# PCB-base.net
KiCad netlist of a schematic drawn in EAGLE
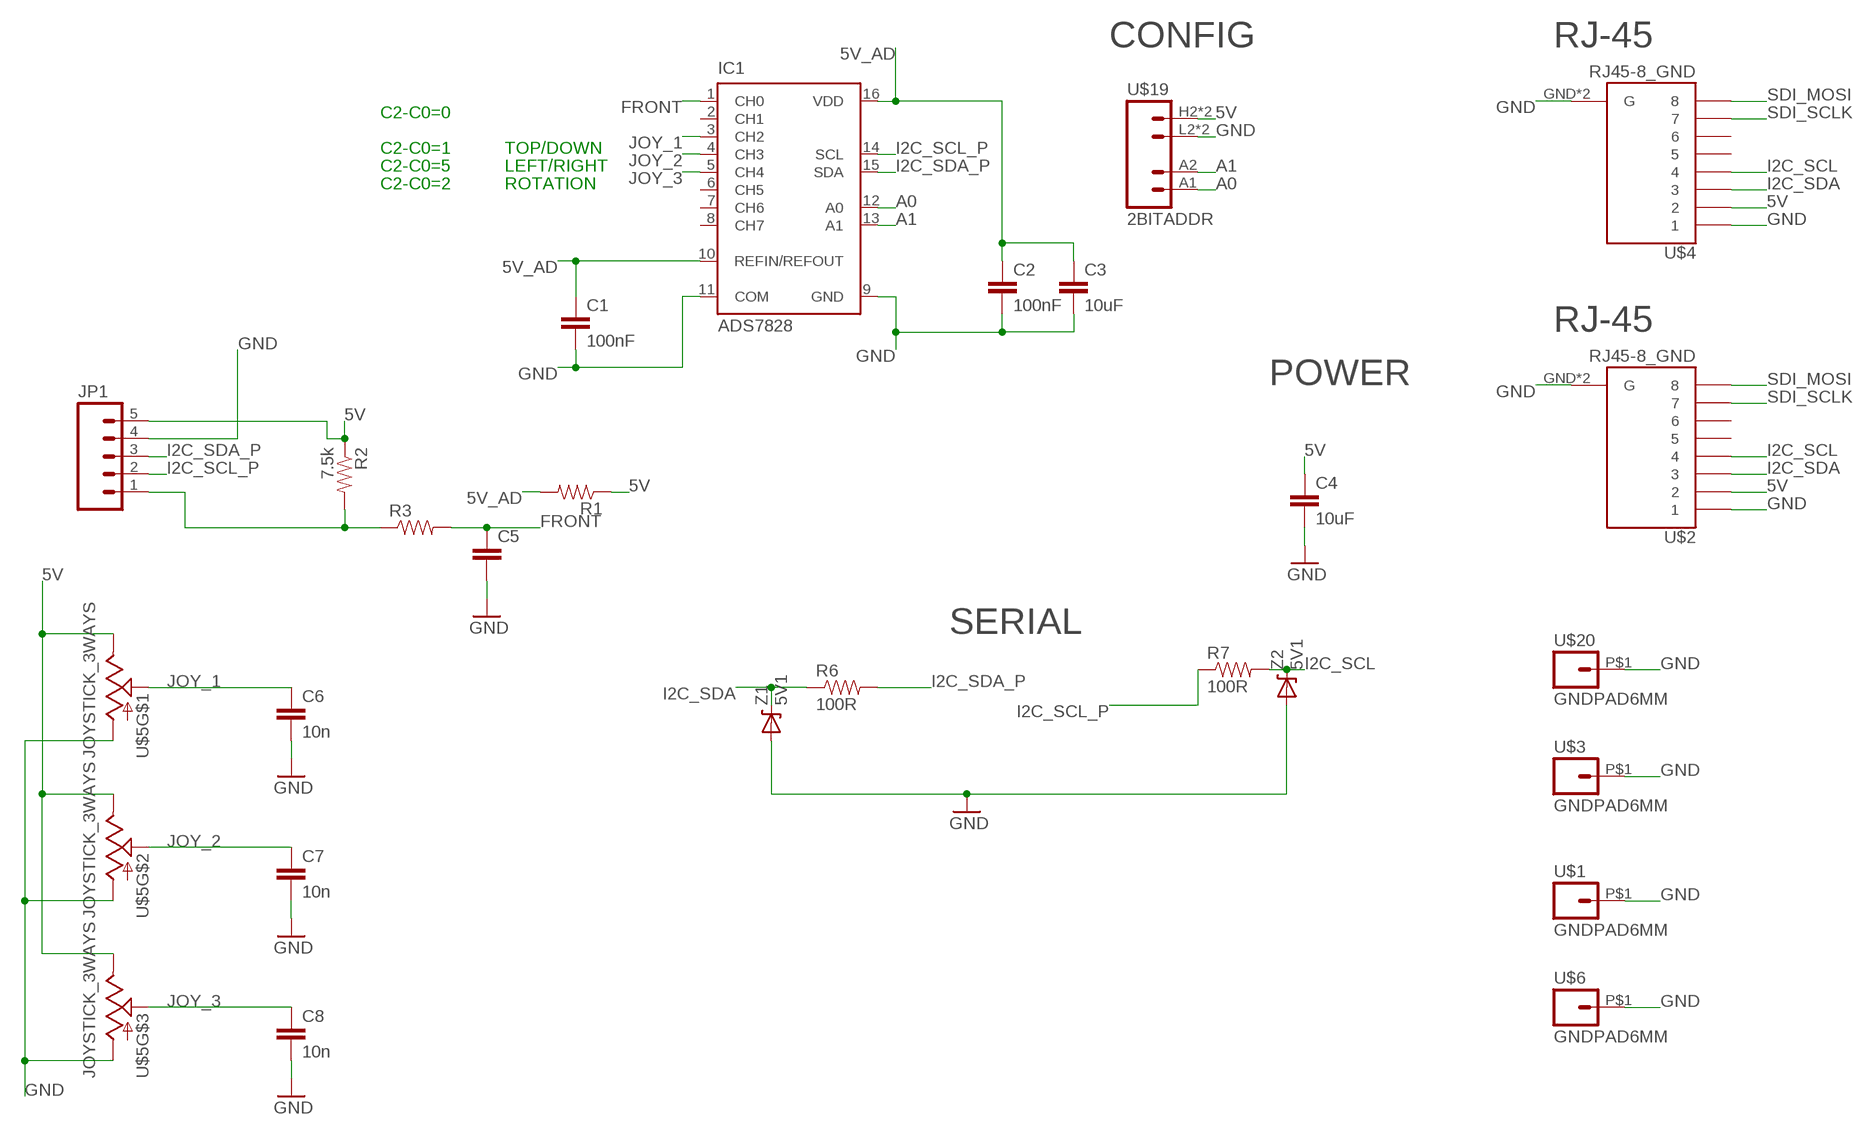
[diagram p0: schematic, sheet 1]

(export (version "E")
  (design (tool "Eeschema 10.0.6"))
  (components
    (comp (ref "C1")
      (value "100nF")
      (footprint "eagle-import:0603-CAP")
      (libsource (lib "eagle-import") (part "CAP0603-CAP"))
    )
    (comp (ref "C2")
      (value "100nF")
      (footprint "eagle-import:0603-CAP")
      (libsource (lib "eagle-import") (part "CAP0603-CAP"))
    )
    (comp (ref "C3")
      (value "10uF")
      (footprint "eagle-import:0805")
      (libsource (lib "eagle-import") (part "CAP0805"))
    )
    (comp (ref "C4")
      (value "10uF")
      (footprint "eagle-import:0805")
      (libsource (lib "eagle-import") (part "CAP0805"))
    )
    (comp (ref "C5")
      (value "CAP0603-CAP")
      (footprint "eagle-import:0603-CAP")
      (libsource (lib "eagle-import") (part "CAP0603-CAP"))
    )
    (comp (ref "C6")
      (value "10n")
      (footprint "eagle-import:0603-CAP")
      (libsource (lib "eagle-import") (part "CAP0603-CAP"))
    )
    (comp (ref "C7")
      (value "10n")
      (footprint "eagle-import:0603-CAP")
      (libsource (lib "eagle-import") (part "CAP0603-CAP"))
    )
    (comp (ref "C8")
      (value "10n")
      (footprint "eagle-import:0603-CAP")
      (libsource (lib "eagle-import") (part "CAP0603-CAP"))
    )
    (comp (ref "IC1")
      (value "ADS7828")
      (footprint "eagle-import:TSSOP16-PW")
      (fields (field (name "MF") "TEXAS INSTRUMENTS") (field (name "MPN") "ADS7828E/250"))
      (libsource (lib "eagle-import") (part "ADS7828"))
    )
    (comp (ref "JP1")
      (value "M05PTH")
      (footprint "eagle-import:1X05")
      (libsource (lib "eagle-import") (part "M05PTH"))
    )
    (comp (ref "R1")
      (value "RESISTOR0603-RES")
      (footprint "eagle-import:0603-RES")
      (libsource (lib "eagle-import") (part "RESISTOR0603-RES"))
    )
    (comp (ref "R2")
      (value "7.5k")
      (footprint "eagle-import:0603-RES")
      (libsource (lib "eagle-import") (part "RESISTOR0603-RES"))
    )
    (comp (ref "R3")
      (value "RESISTOR0603-RES")
      (footprint "eagle-import:0603-RES")
      (libsource (lib "eagle-import") (part "RESISTOR0603-RES"))
    )
    (comp (ref "R6")
      (value "100R")
      (footprint "eagle-import:0603-RES")
      (libsource (lib "eagle-import") (part "RESISTOR0603-RES"))
    )
    (comp (ref "R7")
      (value "100R")
      (footprint "eagle-import:0603-RES")
      (libsource (lib "eagle-import") (part "RESISTOR0603-RES"))
    )
    (comp (ref "U$1")
      (value "GNDPAD6MM")
      (footprint "eagle-import:3.2MMPAD6MM")
      (libsource (lib "eagle-import") (part "GNDPAD6MM"))
    )
    (comp (ref "U$2")
      (value "RJ45-8_GND")
      (footprint "eagle-import:RJ45-8_GND")
      (libsource (lib "eagle-import") (part "RJ45-8_GND"))
    )
    (comp (ref "U$3")
      (value "GNDPAD6MM")
      (footprint "eagle-import:3.2MMPAD6MM")
      (libsource (lib "eagle-import") (part "GNDPAD6MM"))
    )
    (comp (ref "U$4")
      (value "RJ45-8_GND")
      (footprint "eagle-import:RJ45-8_GND")
      (libsource (lib "eagle-import") (part "RJ45-8_GND"))
    )
    (comp (ref "U$5")
      (value "JOYSTICK_3WAYS")
      (footprint "eagle-import:JOYSTICK")
      (libsource (lib "eagle-import") (part "JOYSTICK_3WAYS"))
    )
    (comp (ref "U$6")
      (value "GNDPAD6MM")
      (footprint "eagle-import:3.2MMPAD6MM")
      (libsource (lib "eagle-import") (part "GNDPAD6MM"))
    )
    (comp (ref "U$19")
      (value "2BITADDR")
      (footprint "eagle-import:2BITADDR")
      (libsource (lib "eagle-import") (part "2BITADDR"))
    )
    (comp (ref "U$20")
      (value "GNDPAD6MM")
      (footprint "eagle-import:3.2MMPAD6MM")
      (libsource (lib "eagle-import") (part "GNDPAD6MM"))
    )
    (comp (ref "Z1")
      (value "5V1")
      (footprint "eagle-import:SMB-DIODE")
      (libsource (lib "eagle-import") (part "DIODE-ZENERSMB"))
    )
    (comp (ref "Z2")
      (value "5V1")
      (footprint "eagle-import:SMB-DIODE")
      (libsource (lib "eagle-import") (part "DIODE-ZENERSMB"))
    )
  )
  (nets
    (net (code "1") (name "/5V") (class "Default")
      (node (ref "C4") (pin "1") (pinfunction "1_1") (pintype "passive"))
      (node (ref "JP1") (pin "5") (pinfunction "5_5") (pintype "passive"))
      (node (ref "R1") (pin "1") (pinfunction "1_1") (pintype "passive"))
      (node (ref "R2") (pin "1") (pinfunction "1_1") (pintype "passive"))
      (node (ref "U$19") (pin "H2") (pinfunction "VCC_H2") (pintype "passive"))
      (node (ref "U$19") (pin "H3") (pinfunction "VCC_H3") (pintype "passive"))
      (node (ref "U$2") (pin "2") (pinfunction "2_2") (pintype "bidirectional"))
      (node (ref "U$4") (pin "2") (pinfunction "2_2") (pintype "bidirectional"))
      (node (ref "U$5") (pin "LR_V") (pinfunction "E_LR_V") (pintype "passive"))
      (node (ref "U$5") (pin "ROT_V") (pinfunction "E_ROT_V") (pintype "passive"))
      (node (ref "U$5") (pin "UD_V") (pinfunction "E_UD_V") (pintype "passive"))
    )
    (net (code "2") (name "/5V_AD") (class "Default")
      (node (ref "C1") (pin "1") (pinfunction "1_1") (pintype "passive"))
      (node (ref "C2") (pin "1") (pinfunction "1_1") (pintype "passive"))
      (node (ref "C3") (pin "1") (pinfunction "1_1") (pintype "passive"))
      (node (ref "IC1") (pin "10") (pinfunction "REFIN/REFOUT_10") (pintype "passive"))
      (node (ref "IC1") (pin "16") (pinfunction "VDD_16") (pintype "power_in"))
      (node (ref "R1") (pin "2") (pinfunction "2_2") (pintype "passive"))
    )
    (net (code "3") (name "/A0") (class "Default")
      (node (ref "IC1") (pin "12") (pinfunction "A0_12") (pintype "input"))
      (node (ref "U$19") (pin "A1") (pinfunction "A1_A1") (pintype "passive"))
    )
    (net (code "4") (name "/A1") (class "Default")
      (node (ref "IC1") (pin "13") (pinfunction "A1_13") (pintype "input"))
      (node (ref "U$19") (pin "A2") (pinfunction "A2_A2") (pintype "passive"))
    )
    (net (code "5") (name "/FRONT") (class "Default")
      (node (ref "C5") (pin "1") (pinfunction "1_1") (pintype "passive"))
      (node (ref "IC1") (pin "1") (pinfunction "CH0_1") (pintype "input"))
      (node (ref "R3") (pin "2") (pinfunction "2_2") (pintype "passive"))
    )
    (net (code "6") (name "/I2C_SCL") (class "Default")
      (node (ref "R7") (pin "2") (pinfunction "2_2") (pintype "passive"))
      (node (ref "U$2") (pin "4") (pinfunction "4_4") (pintype "bidirectional"))
      (node (ref "U$4") (pin "4") (pinfunction "4_4") (pintype "bidirectional"))
      (node (ref "Z2") (pin "C") (pinfunction "C_C") (pintype "passive"))
    )
    (net (code "7") (name "/I2C_SCL_P") (class "Default")
      (node (ref "IC1") (pin "14") (pinfunction "SCL_14") (pintype "input"))
      (node (ref "JP1") (pin "2") (pinfunction "2_2") (pintype "passive"))
      (node (ref "R7") (pin "1") (pinfunction "1_1") (pintype "passive"))
    )
    (net (code "8") (name "/I2C_SDA") (class "Default")
      (node (ref "R6") (pin "1") (pinfunction "1_1") (pintype "passive"))
      (node (ref "U$2") (pin "3") (pinfunction "3_3") (pintype "bidirectional"))
      (node (ref "U$4") (pin "3") (pinfunction "3_3") (pintype "bidirectional"))
      (node (ref "Z1") (pin "C") (pinfunction "C_C") (pintype "passive"))
    )
    (net (code "9") (name "/I2C_SDA_P") (class "Default")
      (node (ref "IC1") (pin "15") (pinfunction "SDA_15") (pintype "bidirectional"))
      (node (ref "JP1") (pin "3") (pinfunction "3_3") (pintype "passive"))
      (node (ref "R6") (pin "2") (pinfunction "2_2") (pintype "passive"))
    )
    (net (code "10") (name "/JOY_1") (class "Default")
      (node (ref "C6") (pin "1") (pinfunction "1_1") (pintype "passive"))
      (node (ref "IC1") (pin "3") (pinfunction "CH2_3") (pintype "input"))
      (node (ref "U$5") (pin "LR_C") (pinfunction "S_LR_C") (pintype "passive"))
    )
    (net (code "11") (name "/JOY_2") (class "Default")
      (node (ref "C7") (pin "1") (pinfunction "1_1") (pintype "passive"))
      (node (ref "IC1") (pin "4") (pinfunction "CH3_4") (pintype "input"))
      (node (ref "U$5") (pin "UD_C") (pinfunction "S_UD_C") (pintype "passive"))
    )
    (net (code "12") (name "/JOY_3") (class "Default")
      (node (ref "C8") (pin "1") (pinfunction "1_1") (pintype "passive"))
      (node (ref "IC1") (pin "5") (pinfunction "CH4_5") (pintype "input"))
      (node (ref "U$5") (pin "ROT_C") (pinfunction "S_ROT_C") (pintype "passive"))
    )
    (net (code "13") (name "/SDI_MOSI") (class "Default")
      (node (ref "U$2") (pin "8") (pinfunction "8_8") (pintype "bidirectional"))
      (node (ref "U$4") (pin "8") (pinfunction "8_8") (pintype "bidirectional"))
    )
    (net (code "14") (name "/SDI_SCLK") (class "Default")
      (node (ref "U$2") (pin "7") (pinfunction "7_7") (pintype "bidirectional"))
      (node (ref "U$4") (pin "7") (pinfunction "7_7") (pintype "bidirectional"))
    )
    (net (code "15") (name "GND") (class "Default")
      (node (ref "C1") (pin "2") (pinfunction "2_2") (pintype "passive"))
      (node (ref "C2") (pin "2") (pinfunction "2_2") (pintype "passive"))
      (node (ref "C3") (pin "2") (pinfunction "2_2") (pintype "passive"))
      (node (ref "C4") (pin "2") (pinfunction "2_2") (pintype "passive"))
      (node (ref "C5") (pin "2") (pinfunction "2_2") (pintype "passive"))
      (node (ref "C6") (pin "2") (pinfunction "2_2") (pintype "passive"))
      (node (ref "C7") (pin "2") (pinfunction "2_2") (pintype "passive"))
      (node (ref "C8") (pin "2") (pinfunction "2_2") (pintype "passive"))
      (node (ref "IC1") (pin "11") (pinfunction "COM_11") (pintype "input"))
      (node (ref "IC1") (pin "9") (pinfunction "GND_9") (pintype "power_in"))
      (node (ref "JP1") (pin "4") (pinfunction "4_4") (pintype "passive"))
      (node (ref "U$1") (pin "P$1") (pinfunction "1_P$1") (pintype "passive"))
      (node (ref "U$19") (pin "L2") (pinfunction "GND_L2") (pintype "passive"))
      (node (ref "U$19") (pin "L3") (pinfunction "GND_L3") (pintype "passive"))
      (node (ref "U$2") (pin "1") (pinfunction "1_1") (pintype "bidirectional"))
      (node (ref "U$2") (pin "GND") (pinfunction "G_GND") (pintype "power_in"))
      (node (ref "U$2") (pin "GND1") (pinfunction "G_GND1") (pintype "power_in"))
      (node (ref "U$20") (pin "P$1") (pinfunction "1_P$1") (pintype "passive"))
      (node (ref "U$3") (pin "P$1") (pinfunction "1_P$1") (pintype "passive"))
      (node (ref "U$4") (pin "1") (pinfunction "1_1") (pintype "bidirectional"))
      (node (ref "U$4") (pin "GND") (pinfunction "G_GND") (pintype "power_in"))
      (node (ref "U$4") (pin "GND1") (pinfunction "G_GND1") (pintype "power_in"))
      (node (ref "U$5") (pin "LR_COM") (pinfunction "A_LR_COM") (pintype "passive"))
      (node (ref "U$5") (pin "ROT_COM") (pinfunction "A_ROT_COM") (pintype "passive"))
      (node (ref "U$5") (pin "UD_COM") (pinfunction "A_UD_COM") (pintype "passive"))
      (node (ref "U$6") (pin "P$1") (pinfunction "1_P$1") (pintype "passive"))
      (node (ref "Z1") (pin "A") (pinfunction "A_A") (pintype "passive"))
      (node (ref "Z2") (pin "A") (pinfunction "A_A") (pintype "passive"))
    )
    (net (code "16") (name "Net-(JP1-Pad1)") (class "Default")
      (node (ref "JP1") (pin "1") (pinfunction "1_1") (pintype "passive"))
      (node (ref "R2") (pin "2") (pinfunction "2_2") (pintype "passive"))
      (node (ref "R3") (pin "1") (pinfunction "1_1") (pintype "passive"))
    )
    (net (code "17") (name "unconnected-(IC1-CH1-Pad2)") (class "Default")
      (node (ref "IC1") (pin "2") (pinfunction "CH1_2") (pintype "input"))
    )
    (net (code "18") (name "unconnected-(IC1-CH5-Pad6)") (class "Default")
      (node (ref "IC1") (pin "6") (pinfunction "CH5_6") (pintype "input"))
    )
    (net (code "19") (name "unconnected-(IC1-CH6-Pad7)") (class "Default")
      (node (ref "IC1") (pin "7") (pinfunction "CH6_7") (pintype "input"))
    )
    (net (code "20") (name "unconnected-(IC1-CH7-Pad8)") (class "Default")
      (node (ref "IC1") (pin "8") (pinfunction "CH7_8") (pintype "input"))
    )
    (net (code "21") (name "unconnected-(U$2-Pad5)") (class "Default")
      (node (ref "U$2") (pin "5") (pinfunction "5_5") (pintype "bidirectional"))
    )
    (net (code "22") (name "unconnected-(U$2-Pad6)") (class "Default")
      (node (ref "U$2") (pin "6") (pinfunction "6_6") (pintype "bidirectional"))
    )
    (net (code "23") (name "unconnected-(U$4-Pad5)") (class "Default")
      (node (ref "U$4") (pin "5") (pinfunction "5_5") (pintype "bidirectional"))
    )
    (net (code "24") (name "unconnected-(U$4-Pad6)") (class "Default")
      (node (ref "U$4") (pin "6") (pinfunction "6_6") (pintype "bidirectional"))
    )
  )
)
